# LED0805-1_Sch.net
KiCad netlist of a schematic drawn in Altium Designer
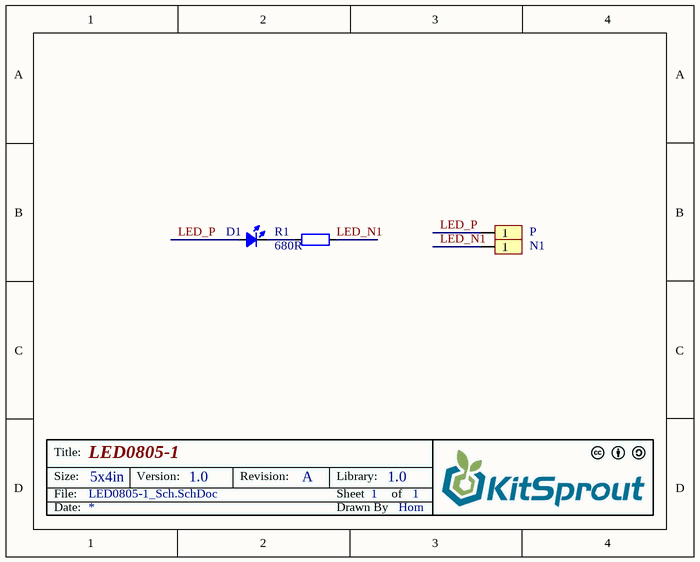
[diagram p0: LED0805-1_Sch.SchDoc]

(export (version "E")
  (design (tool "Eeschema 10.0.6"))
  (components
    (comp (ref "D1")
      (value "LED_0805")
      (footprint "PCB_ActiveLED:LED_0805_BLUE")
      (description "LED")
      (libsource (lib "SCH_Active") (part "LED_0805"))
    )
    (comp (ref "N1")
      (value "HDR-PAD_2.54")
      (footprint "PCB_ConnectorHDR:HDR-PAD_2.54")
      (description "Header")
      (libsource (lib "SCH_ConnectorHDR") (part "HDR-PAD_2.54"))
    )
    (comp (ref "P")
      (value "HDR-PAD_2.54")
      (footprint "PCB_ConnectorHDR:HDR-PAD_2.54")
      (description "Header")
      (libsource (lib "SCH_ConnectorHDR") (part "HDR-PAD_2.54"))
    )
    (comp (ref "R1")
      (value "680R")
      (footprint "PCB_PassiveRes:RES_0805")
      (description "Resistor")
      (fields (field (name "Comment") "Res_0805"))
      (libsource (lib "SCH_Passive") (part "Res_0805"))
    )
  )
  (nets
    (net (code "1") (name "/LED_N1") (class "Default")
      (node (ref "N1") (pin "1") (pinfunction "1_1") (pintype "passive"))
      (node (ref "R1") (pin "2") (pinfunction "2_2") (pintype "passive"))
    )
    (net (code "2") (name "/LED_P") (class "Default")
      (node (ref "D1") (pin "1") (pinfunction "A_1") (pintype "passive"))
      (node (ref "P") (pin "1") (pinfunction "1_1") (pintype "passive"))
    )
    (net (code "3") (name "Net-(D1-K)") (class "Default")
      (node (ref "D1") (pin "2") (pinfunction "K_2") (pintype "passive"))
      (node (ref "R1") (pin "1") (pinfunction "1_1") (pintype "passive"))
    )
  )
)
